# electric_xmas.net
KiCad netlist of a schematic drawn in EAGLE
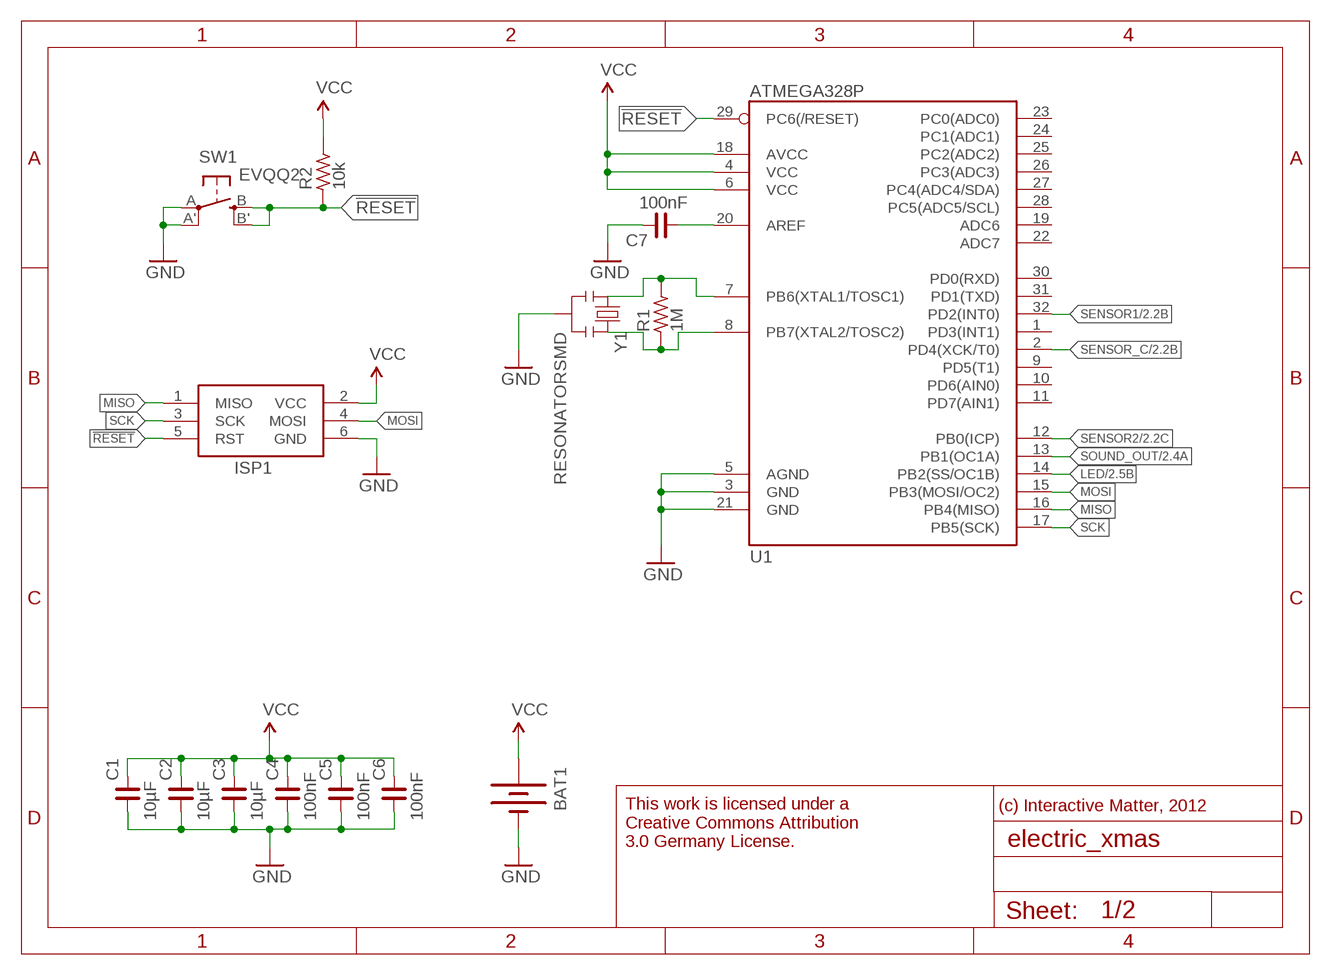
[diagram p0: schematic, sheet 1]
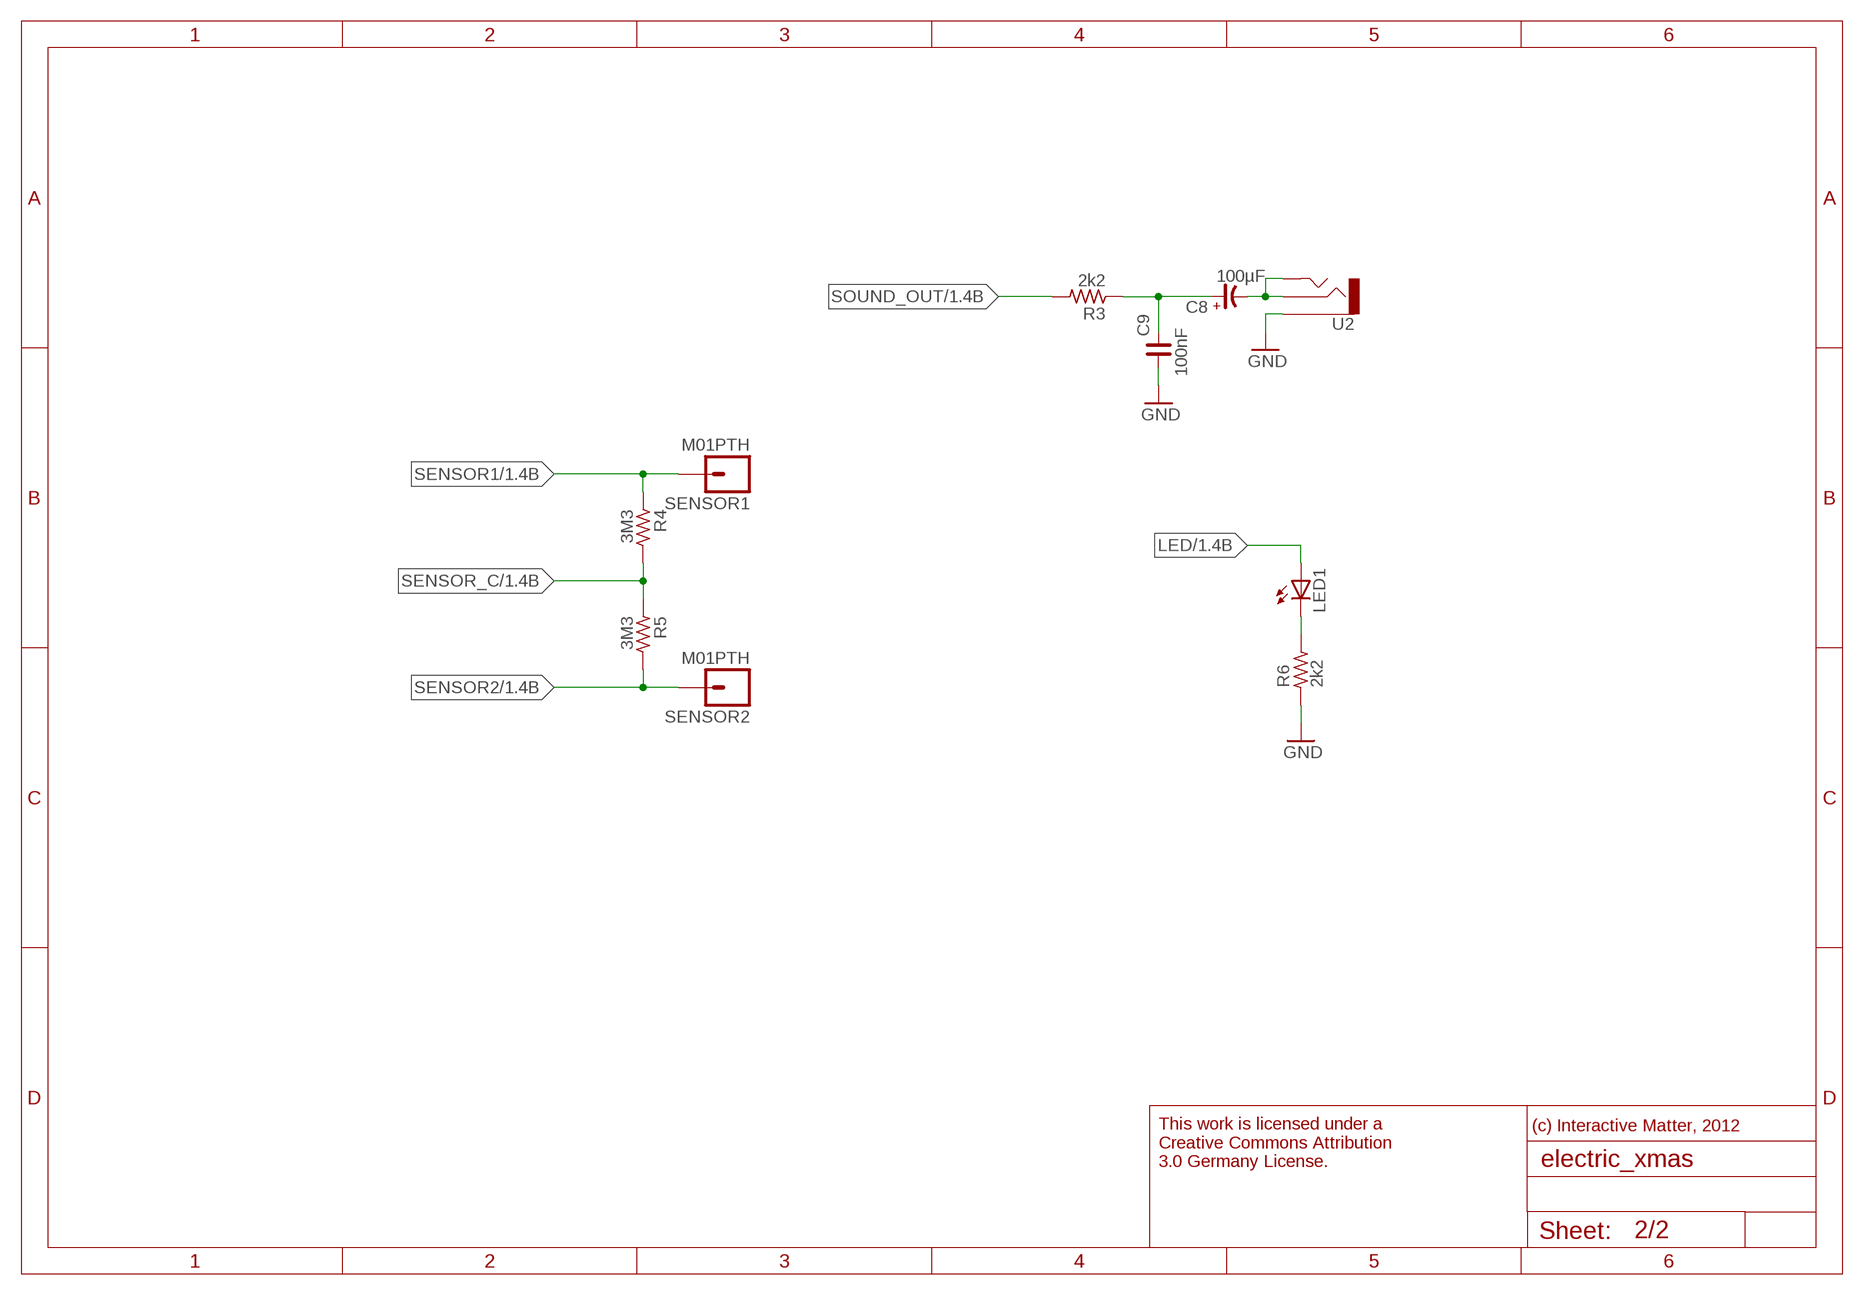
[diagram p1: schematic, sheet 2]

(export (version "E")
  (design (tool "Eeschema 10.0.6"))
  (components
    (comp (ref "BAT1")
      (value "BATTERY20SMD")
      (footprint "eagle-import:BATTCON_20MM")
      (libsource (lib "eagle-import") (part "BATTERY20SMD"))
    )
    (comp (ref "C1")
      (value "10µF")
      (footprint "eagle-import:C0805")
      (libsource (lib "eagle-import") (part "C_0805"))
    )
    (comp (ref "C2")
      (value "10µF")
      (footprint "eagle-import:C0805")
      (libsource (lib "eagle-import") (part "C_0805"))
    )
    (comp (ref "C3")
      (value "10µF")
      (footprint "eagle-import:C0805")
      (libsource (lib "eagle-import") (part "C_0805"))
    )
    (comp (ref "C4")
      (value "100nF")
      (footprint "eagle-import:C0805")
      (libsource (lib "eagle-import") (part "C_0805"))
    )
    (comp (ref "C5")
      (value "100nF")
      (footprint "eagle-import:C0805")
      (libsource (lib "eagle-import") (part "C_0805"))
    )
    (comp (ref "C6")
      (value "100nF")
      (footprint "eagle-import:C0805")
      (libsource (lib "eagle-import") (part "C_0805"))
    )
    (comp (ref "C7")
      (value "100nF")
      (footprint "eagle-import:C0805")
      (libsource (lib "eagle-import") (part "C_0805"))
    )
    (comp (ref "ISP1")
      (value "AVRISP-6")
      (footprint "eagle-import:AVRISP")
      (libsource (lib "eagle-import") (part "AVRISP-6"))
    )
    (comp (ref "R1")
      (value "1M")
      (footprint "eagle-import:R0805")
      (libsource (lib "eagle-import") (part "R_0805"))
    )
    (comp (ref "R2")
      (value "10k")
      (footprint "eagle-import:R0805")
      (libsource (lib "eagle-import") (part "R_0805"))
    )
    (comp (ref "SW1")
      (value "EVQQ2")
      (footprint "eagle-import:EVQ-Q2")
      (libsource (lib "eagle-import") (part "EVQQ2"))
    )
    (comp (ref "U1")
      (value "ATMEGA328P")
      (footprint "eagle-import:TQFP32-08")
      (libsource (lib "eagle-import") (part "ATMEGA168"))
    )
    (comp (ref "Y1")
      (value "RESONATORSMD")
      (footprint "eagle-import:RESONATOR-SMD")
      (libsource (lib "eagle-import") (part "RESONATORSMD"))
    )
    (comp (ref "C8")
      (value "100µF")
      (footprint "eagle-import:CSV-D")
      (libsource (lib "eagle-import") (part "CP_SV-D"))
    )
    (comp (ref "C9")
      (value "100nF")
      (footprint "eagle-import:C0805")
      (libsource (lib "eagle-import") (part "C_0805"))
    )
    (comp (ref "LED1")
      (value "LEDLUMEXGW")
      (footprint "eagle-import:LUMEX_GW_BOTTOM")
      (libsource (lib "eagle-import") (part "LEDLUMEXGW"))
    )
    (comp (ref "R3")
      (value "2k2")
      (footprint "eagle-import:R0805")
      (libsource (lib "eagle-import") (part "R_0805"))
    )
    (comp (ref "R4")
      (value "3M3")
      (footprint "eagle-import:R0805")
      (libsource (lib "eagle-import") (part "R_0805"))
    )
    (comp (ref "R5")
      (value "3M3")
      (footprint "eagle-import:R0805")
      (libsource (lib "eagle-import") (part "R_0805"))
    )
    (comp (ref "R6")
      (value "2k2")
      (footprint "eagle-import:R0805")
      (libsource (lib "eagle-import") (part "R_0805"))
    )
    (comp (ref "SENSOR1")
      (value "M01PTH")
      (footprint "eagle-import:1X01")
      (libsource (lib "eagle-import") (part "M01PTH"))
    )
    (comp (ref "SENSOR2")
      (value "M01PTH")
      (footprint "eagle-import:1X01")
      (libsource (lib "eagle-import") (part "M01PTH"))
    )
    (comp (ref "U2")
      (value "AUDIO-JACK")
      (footprint "eagle-import:LUMBERGRC-5325A")
      (libsource (lib "eagle-import") (part "AUDIO-JACK"))
    )
  )
  (nets
    (net (code "1") (name "GND") (class "Default")
      (node (ref "BAT1") (pin "2") (pinfunction "-_2") (pintype "power_in"))
      (node (ref "C1") (pin "1") (pinfunction "1_1") (pintype "passive"))
      (node (ref "C2") (pin "1") (pinfunction "1_1") (pintype "passive"))
      (node (ref "C3") (pin "1") (pinfunction "1_1") (pintype "passive"))
      (node (ref "C4") (pin "1") (pinfunction "1_1") (pintype "passive"))
      (node (ref "C5") (pin "1") (pinfunction "1_1") (pintype "passive"))
      (node (ref "C6") (pin "1") (pinfunction "1_1") (pintype "passive"))
      (node (ref "C7") (pin "2") (pinfunction "2_2") (pintype "passive"))
      (node (ref "C9") (pin "1") (pinfunction "1_1") (pintype "passive"))
      (node (ref "ISP1") (pin "6") (pinfunction "GND_6") (pintype "power_in"))
      (node (ref "R6") (pin "1") (pinfunction "1_1") (pintype "passive"))
      (node (ref "SW1") (pin "A") (pinfunction "P_A") (pintype "passive"))
      (node (ref "SW1") (pin "A'") (pinfunction "P1_A'") (pintype "passive"))
      (node (ref "U1") (pin "21") (pinfunction "GND_21") (pintype "bidirectional"))
      (node (ref "U1") (pin "3") (pinfunction "GND_3") (pintype "bidirectional"))
      (node (ref "U1") (pin "5") (pinfunction "AGND_5") (pintype "bidirectional"))
      (node (ref "U2") (pin "1") (pinfunction "1_1") (pintype "bidirectional"))
      (node (ref "U2") (pin "2") (pinfunction "1_2") (pintype "bidirectional"))
      (node (ref "Y1") (pin "2") (pinfunction "2_2") (pintype "passive"))
    )
    (net (code "2") (name "LED") (class "Default")
      (node (ref "LED1") (pin "A") (pinfunction "A_A") (pintype "passive"))
      (node (ref "U1") (pin "14") (pinfunction "PB2(SS/OC1B)_14") (pintype "bidirectional"))
    )
    (net (code "3") (name "MISO") (class "Default")
      (node (ref "ISP1") (pin "1") (pinfunction "MISO_1") (pintype "input"))
      (node (ref "U1") (pin "16") (pinfunction "PB4(MISO)_16") (pintype "bidirectional"))
    )
    (net (code "4") (name "MOSI") (class "Default")
      (node (ref "ISP1") (pin "4") (pinfunction "MOSI_4") (pintype "output"))
      (node (ref "U1") (pin "15") (pinfunction "PB3(MOSI/OC2)_15") (pintype "bidirectional"))
    )
    (net (code "5") (name "Net-(C8-Pad+)") (class "Default")
      (node (ref "C8") (pin "+") (pinfunction "+_+") (pintype "passive"))
      (node (ref "C9") (pin "2") (pinfunction "2_2") (pintype "passive"))
      (node (ref "R3") (pin "1") (pinfunction "1_1") (pintype "passive"))
    )
    (net (code "6") (name "Net-(LED1-PadC)") (class "Default")
      (node (ref "LED1") (pin "C") (pinfunction "C_C") (pintype "passive"))
      (node (ref "R6") (pin "2") (pinfunction "2_2") (pintype "passive"))
    )
    (net (code "7") (name "Net-(U1-AREF)") (class "Default")
      (node (ref "C7") (pin "1") (pinfunction "1_1") (pintype "passive"))
      (node (ref "U1") (pin "20") (pinfunction "AREF_20") (pintype "bidirectional"))
    )
    (net (code "8") (name "Net-(U1-PB6(XTAL1{slash}TOSC1))") (class "Default")
      (node (ref "R1") (pin "2") (pinfunction "2_2") (pintype "passive"))
      (node (ref "U1") (pin "7") (pinfunction "PB6(XTAL1/TOSC1)_7") (pintype "bidirectional"))
      (node (ref "Y1") (pin "1") (pinfunction "1_1") (pintype "passive"))
    )
    (net (code "9") (name "Net-(U1-PB7(XTAL2{slash}TOSC2))") (class "Default")
      (node (ref "R1") (pin "1") (pinfunction "1_1") (pintype "passive"))
      (node (ref "U1") (pin "8") (pinfunction "PB7(XTAL2/TOSC2)_8") (pintype "bidirectional"))
      (node (ref "Y1") (pin "3") (pinfunction "3_3") (pintype "passive"))
    )
    (net (code "10") (name "Net-(U2-5)") (class "Default")
      (node (ref "C8") (pin "-") (pinfunction "-_-") (pintype "passive"))
      (node (ref "U2") (pin "3") (pinfunction "5_3") (pintype "bidirectional"))
      (node (ref "U2") (pin "4@1") (pinfunction "2_4@1") (pintype "bidirectional"))
      (node (ref "U2") (pin "4@2") (pinfunction "2_4@2") (pintype "bidirectional"))
    )
    (net (code "11") (name "SCK") (class "Default")
      (node (ref "ISP1") (pin "3") (pinfunction "SCK_3") (pintype "output"))
      (node (ref "U1") (pin "17") (pinfunction "PB5(SCK)_17") (pintype "bidirectional"))
    )
    (net (code "12") (name "SENSOR1") (class "Default")
      (node (ref "R4") (pin "1") (pinfunction "1_1") (pintype "passive"))
      (node (ref "SENSOR1") (pin "1") (pinfunction "1_1") (pintype "passive"))
      (node (ref "U1") (pin "32") (pinfunction "PD2(INT0)_32") (pintype "bidirectional"))
    )
    (net (code "13") (name "SENSOR2") (class "Default")
      (node (ref "R5") (pin "2") (pinfunction "2_2") (pintype "passive"))
      (node (ref "SENSOR2") (pin "1") (pinfunction "1_1") (pintype "passive"))
      (node (ref "U1") (pin "12") (pinfunction "PB0(ICP)_12") (pintype "bidirectional"))
    )
    (net (code "14") (name "SENSOR_C") (class "Default")
      (node (ref "R4") (pin "2") (pinfunction "2_2") (pintype "passive"))
      (node (ref "R5") (pin "1") (pinfunction "1_1") (pintype "passive"))
      (node (ref "U1") (pin "2") (pinfunction "PD4(XCK/T0)_2") (pintype "bidirectional"))
    )
    (net (code "15") (name "SOUND_OUT") (class "Default")
      (node (ref "R3") (pin "2") (pinfunction "2_2") (pintype "passive"))
      (node (ref "U1") (pin "13") (pinfunction "PB1(OC1A)_13") (pintype "bidirectional"))
    )
    (net (code "16") (name "VCC") (class "Default")
      (node (ref "BAT1") (pin "1") (pinfunction "+_1") (pintype "power_in"))
      (node (ref "C1") (pin "2") (pinfunction "2_2") (pintype "passive"))
      (node (ref "C2") (pin "2") (pinfunction "2_2") (pintype "passive"))
      (node (ref "C3") (pin "2") (pinfunction "2_2") (pintype "passive"))
      (node (ref "C4") (pin "2") (pinfunction "2_2") (pintype "passive"))
      (node (ref "C5") (pin "2") (pinfunction "2_2") (pintype "passive"))
      (node (ref "C6") (pin "2") (pinfunction "2_2") (pintype "passive"))
      (node (ref "ISP1") (pin "2") (pinfunction "VCC_2") (pintype "power_in"))
      (node (ref "R2") (pin "2") (pinfunction "2_2") (pintype "passive"))
      (node (ref "U1") (pin "18") (pinfunction "AVCC_18") (pintype "bidirectional"))
      (node (ref "U1") (pin "4") (pinfunction "VCC_4") (pintype "bidirectional"))
      (node (ref "U1") (pin "6") (pinfunction "VCC_6") (pintype "bidirectional"))
    )
    (net (code "17") (name "unconnected-(U1-ADC6-Pad19)") (class "Default")
      (node (ref "U1") (pin "19") (pinfunction "ADC6_19") (pintype "bidirectional"))
    )
    (net (code "18") (name "unconnected-(U1-ADC7-Pad22)") (class "Default")
      (node (ref "U1") (pin "22") (pinfunction "ADC7_22") (pintype "bidirectional"))
    )
    (net (code "19") (name "unconnected-(U1-PC0(ADC0)-Pad23)") (class "Default")
      (node (ref "U1") (pin "23") (pinfunction "PC0(ADC0)_23") (pintype "bidirectional"))
    )
    (net (code "20") (name "unconnected-(U1-PC1(ADC1)-Pad24)") (class "Default")
      (node (ref "U1") (pin "24") (pinfunction "PC1(ADC1)_24") (pintype "bidirectional"))
    )
    (net (code "21") (name "unconnected-(U1-PC2(ADC2)-Pad25)") (class "Default")
      (node (ref "U1") (pin "25") (pinfunction "PC2(ADC2)_25") (pintype "bidirectional"))
    )
    (net (code "22") (name "unconnected-(U1-PC3(ADC3)-Pad26)") (class "Default")
      (node (ref "U1") (pin "26") (pinfunction "PC3(ADC3)_26") (pintype "bidirectional"))
    )
    (net (code "23") (name "unconnected-(U1-PC4(ADC4{slash}SDA)-Pad27)") (class "Default")
      (node (ref "U1") (pin "27") (pinfunction "PC4(ADC4/SDA)_27") (pintype "bidirectional"))
    )
    (net (code "24") (name "unconnected-(U1-PC5(ADC5{slash}SCL)-Pad28)") (class "Default")
      (node (ref "U1") (pin "28") (pinfunction "PC5(ADC5/SCL)_28") (pintype "bidirectional"))
    )
    (net (code "25") (name "unconnected-(U1-PD0(RXD)-Pad30)") (class "Default")
      (node (ref "U1") (pin "30") (pinfunction "PD0(RXD)_30") (pintype "bidirectional"))
    )
    (net (code "26") (name "unconnected-(U1-PD1(TXD)-Pad31)") (class "Default")
      (node (ref "U1") (pin "31") (pinfunction "PD1(TXD)_31") (pintype "bidirectional"))
    )
    (net (code "27") (name "unconnected-(U1-PD3(INT1)-Pad1)") (class "Default")
      (node (ref "U1") (pin "1") (pinfunction "PD3(INT1)_1") (pintype "bidirectional"))
    )
    (net (code "28") (name "unconnected-(U1-PD5(T1)-Pad9)") (class "Default")
      (node (ref "U1") (pin "9") (pinfunction "PD5(T1)_9") (pintype "bidirectional"))
    )
    (net (code "29") (name "unconnected-(U1-PD6(AIN0)-Pad10)") (class "Default")
      (node (ref "U1") (pin "10") (pinfunction "PD6(AIN0)_10") (pintype "bidirectional"))
    )
    (net (code "30") (name "unconnected-(U1-PD7(AIN1)-Pad11)") (class "Default")
      (node (ref "U1") (pin "11") (pinfunction "PD7(AIN1)_11") (pintype "bidirectional"))
    )
    (net (code "31") (name "~{RESET}") (class "Default")
      (node (ref "ISP1") (pin "5") (pinfunction "RST_5") (pintype "output"))
      (node (ref "R2") (pin "1") (pinfunction "1_1") (pintype "passive"))
      (node (ref "SW1") (pin "B") (pinfunction "S_B") (pintype "passive"))
      (node (ref "SW1") (pin "B'") (pinfunction "S1_B'") (pintype "passive"))
      (node (ref "U1") (pin "29") (pinfunction "PC6(/RESET)_29") (pintype "bidirectional"))
    )
  )
)
